# Sheet1.net
KiCad netlist of a schematic drawn in Altium Designer
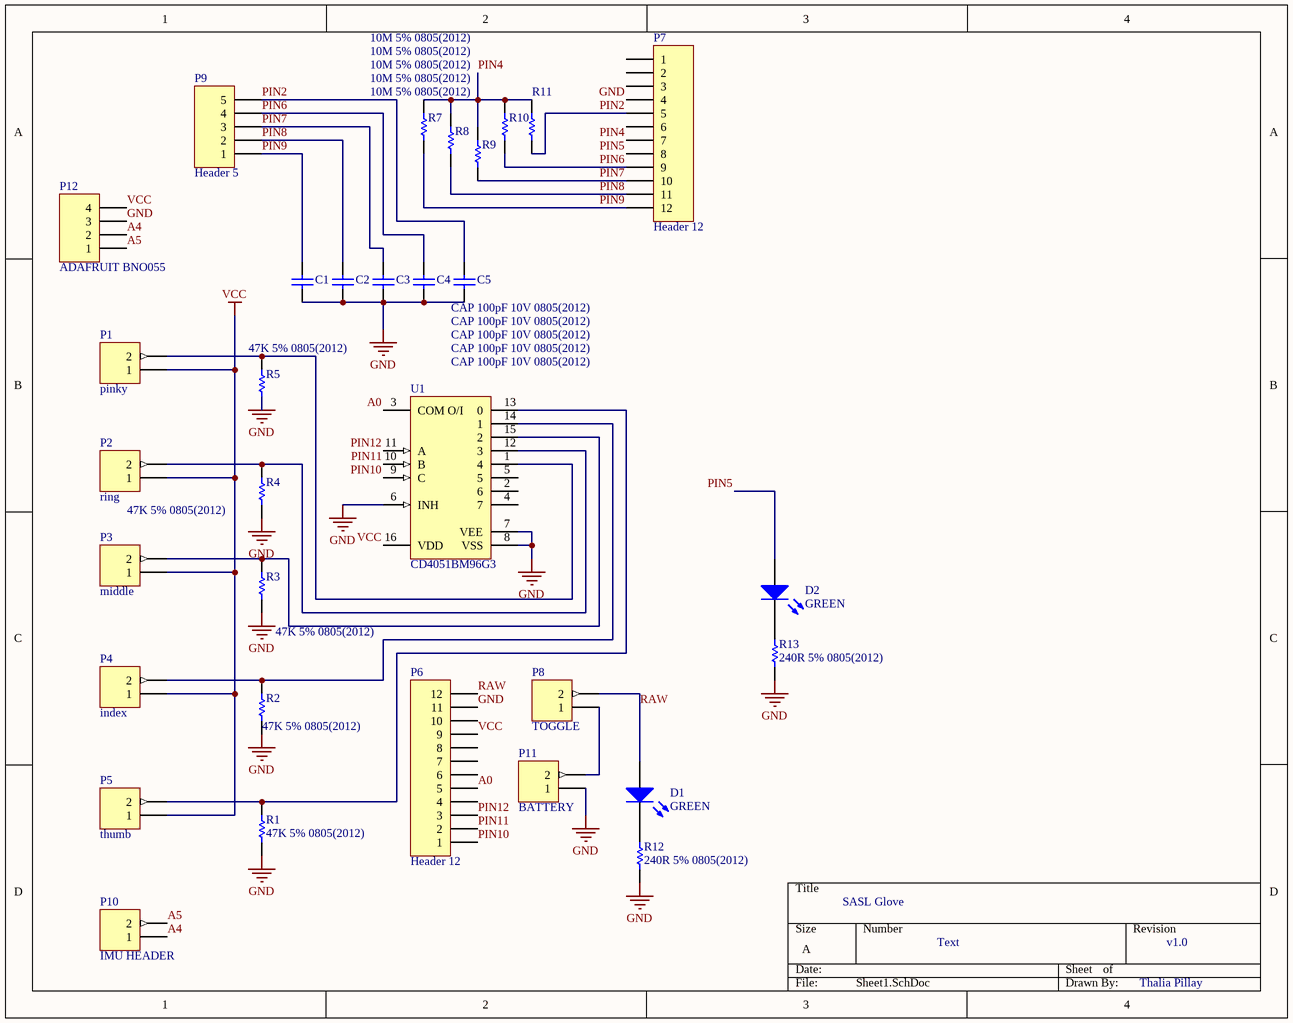
[diagram p0: Sheet1.SchDoc]

(export (version "E")
  (design (tool "Eeschema 10.0.6"))
  (components
    (comp (ref "C1")
      (value "CAP 100pF 10V 0805(2012)")
      (footprint "CAPC0805(2012)100_M")
      (description "CAP 100pF 10V ±5% 0805 (2012 Metric) Thickness 1mm SMD")
      (fields (field (name "TOLERANCE") "Â±5%"))
      (libsource (lib "Altium Content Vault") (part "CAP"))
    )
    (comp (ref "C2")
      (value "CAP 100pF 10V 0805(2012)")
      (footprint "CAPC0805(2012)100_M")
      (description "CAP 100pF 10V ±5% 0805 (2012 Metric) Thickness 1mm SMD")
      (fields (field (name "TOLERANCE") "Â±5%"))
      (libsource (lib "Altium Content Vault") (part "CAP"))
    )
    (comp (ref "C3")
      (value "CAP 100pF 10V 0805(2012)")
      (footprint "CAPC0805(2012)100_M")
      (description "CAP 100pF 10V ±5% 0805 (2012 Metric) Thickness 1mm SMD")
      (fields (field (name "TOLERANCE") "Â±5%"))
      (libsource (lib "Altium Content Vault") (part "CAP"))
    )
    (comp (ref "C4")
      (value "CAP 100pF 10V 0805(2012)")
      (footprint "CAPC0805(2012)100_M")
      (description "CAP 100pF 10V ±5% 0805 (2012 Metric) Thickness 1mm SMD")
      (fields (field (name "TOLERANCE") "Â±5%"))
      (libsource (lib "Altium Content Vault") (part "CAP"))
    )
    (comp (ref "C5")
      (value "CAP 100pF 10V 0805(2012)")
      (footprint "CAPC0805(2012)100_M")
      (description "CAP 100pF 10V ±5% 0805 (2012 Metric) Thickness 1mm SMD")
      (fields (field (name "TOLERANCE") "Â±5%"))
      (libsource (lib "Altium Content Vault") (part "CAP"))
    )
    (comp (ref "D1")
      (value "GREEN")
      (footprint "3.2X1.6X1.1")
      (description "Typical RED, GREEN, YELLOW, AMBER GaAs LED")
      (fields (field (name "PUBLISHER") "Altium Limited"))
      (libsource (lib "Miscellaneous Devices") (part "LED2"))
    )
    (comp (ref "D2")
      (value "GREEN")
      (footprint "3.2X1.6X1.1")
      (description "Typical RED, GREEN, YELLOW, AMBER GaAs LED")
      (fields (field (name "PUBLISHER") "Altium Limited"))
      (libsource (lib "Miscellaneous Devices") (part "LED2"))
    )
    (comp (ref "P1")
      (value "pinky")
      (footprint "HDR1X2")
      (description "Header, 2-Pin")
      (fields (field (name "PUBLISHER") "Altium Limited"))
      (libsource (lib "Miscellaneous Connectors") (part "Header 2"))
    )
    (comp (ref "P2")
      (value "ring")
      (footprint "HDR1X2")
      (description "Header, 2-Pin")
      (fields (field (name "PUBLISHER") "Altium Limited"))
      (libsource (lib "Miscellaneous Connectors") (part "Header 2"))
    )
    (comp (ref "P3")
      (value "middle")
      (footprint "HDR1X2")
      (description "Header, 2-Pin")
      (fields (field (name "PUBLISHER") "Altium Limited"))
      (libsource (lib "Miscellaneous Connectors") (part "Header 2"))
    )
    (comp (ref "P4")
      (value "index")
      (footprint "HDR1X2")
      (description "Header, 2-Pin")
      (fields (field (name "PUBLISHER") "Altium Limited"))
      (libsource (lib "Miscellaneous Connectors") (part "Header 2"))
    )
    (comp (ref "P5")
      (value "thumb")
      (footprint "HDR1X2")
      (description "Header, 2-Pin")
      (fields (field (name "PUBLISHER") "Altium Limited"))
      (libsource (lib "Miscellaneous Connectors") (part "Header 2"))
    )
    (comp (ref "P6")
      (value "Header 12")
      (footprint "HDR1X12")
      (description "Header, 12-Pin")
      (fields (field (name "PUBLISHER") "Altium Limited"))
      (libsource (lib "") (part "Header 12_1"))
    )
    (comp (ref "P7")
      (value "Header 12")
      (footprint "HDR1X12")
      (description "Header, 12-Pin")
      (fields (field (name "PUBLISHER") "Altium Limited"))
      (libsource (lib "Miscellaneous Connectors") (part "Header 12"))
    )
    (comp (ref "P8")
      (value "TOGGLE")
      (footprint "HDR1X2")
      (description "Header, 2-Pin")
      (fields (field (name "PUBLISHER") "Altium Limited"))
      (libsource (lib "Miscellaneous Connectors") (part "Header 2"))
    )
    (comp (ref "P9")
      (value "Header 5")
      (footprint "HDR1X5")
      (description "Header, 5-Pin")
      (fields (field (name "PUBLISHER") "Altium Limited"))
      (libsource (lib "Miscellaneous Connectors") (part "Header 5"))
    )
    (comp (ref "P10")
      (value "IMU HEADER")
      (footprint "HDR1X2")
      (description "Header, 2-Pin")
      (fields (field (name "PUBLISHER") "Altium Limited"))
      (libsource (lib "Miscellaneous Connectors") (part "Header 2"))
    )
    (comp (ref "P11")
      (value "BATTERY")
      (footprint "HDR1X2")
      (description "Header, 2-Pin")
      (fields (field (name "PUBLISHER") "Altium Limited"))
      (libsource (lib "Miscellaneous Connectors") (part "Header 2"))
    )
    (comp (ref "P12")
      (value "ADAFRUIT BNO055")
      (footprint "HDR1X4")
      (description "Header, 4-Pin")
      (fields (field (name "PUBLISHER") "Altium Limited"))
      (libsource (lib "Miscellaneous Connectors") (part "Header 4"))
    )
    (comp (ref "R1")
      (value "47K 5% 0805(2012)")
      (footprint "RESC0805(2012)_L")
      (description "47K 0.125W 5% 0805 (2012 Metric)  SMD")
      (fields (field (name "TOLERANCE") "5 %") (field (name "POWER") "0.125 W"))
      (libsource (lib "Altium Content Vault") (part "RES"))
    )
    (comp (ref "R2")
      (value "47K 5% 0805(2012)")
      (footprint "RESC0805(2012)_L")
      (description "47K 0.125W 5% 0805 (2012 Metric)  SMD")
      (fields (field (name "TOLERANCE") "5 %") (field (name "POWER") "0.125 W"))
      (libsource (lib "Altium Content Vault") (part "RES"))
    )
    (comp (ref "R3")
      (value "47K 5% 0805(2012)")
      (footprint "RESC0805(2012)_L")
      (description "47K 0.125W 5% 0805 (2012 Metric)  SMD")
      (fields (field (name "TOLERANCE") "5 %") (field (name "POWER") "0.125 W"))
      (libsource (lib "Altium Content Vault") (part "RES"))
    )
    (comp (ref "R4")
      (value "47K 5% 0805(2012)")
      (footprint "RESC0805(2012)_L")
      (description "47K 0.125W 5% 0805 (2012 Metric)  SMD")
      (fields (field (name "TOLERANCE") "5 %") (field (name "POWER") "0.125 W"))
      (libsource (lib "Altium Content Vault") (part "RES"))
    )
    (comp (ref "R5")
      (value "47K 5% 0805(2012)")
      (footprint "RESC0805(2012)_L")
      (description "47K 0.125W 5% 0805 (2012 Metric)  SMD")
      (fields (field (name "TOLERANCE") "5 %") (field (name "POWER") "0.125 W"))
      (libsource (lib "Altium Content Vault") (part "RES"))
    )
    (comp (ref "R7")
      (value "10M 5% 0805(2012)")
      (footprint "RESC0805(2012)_M")
      (description "10M 0.125W 5% 0805 (2012 Metric)  SMD")
      (fields (field (name "POWER") "0.125 W") (field (name "TOLERANCE") "5 %"))
      (libsource (lib "Altium Content Vault") (part "RES"))
    )
    (comp (ref "R8")
      (value "10M 5% 0805(2012)")
      (footprint "RESC0805(2012)_M")
      (description "10M 0.125W 5% 0805 (2012 Metric)  SMD")
      (fields (field (name "POWER") "0.125 W") (field (name "TOLERANCE") "5 %"))
      (libsource (lib "Altium Content Vault") (part "RES"))
    )
    (comp (ref "R9")
      (value "10M 5% 0805(2012)")
      (footprint "RESC0805(2012)_M")
      (description "10M 0.125W 5% 0805 (2012 Metric)  SMD")
      (fields (field (name "POWER") "0.125 W") (field (name "TOLERANCE") "5 %"))
      (libsource (lib "Altium Content Vault") (part "RES"))
    )
    (comp (ref "R10")
      (value "10M 5% 0805(2012)")
      (footprint "RESC0805(2012)_M")
      (description "10M 0.125W 5% 0805 (2012 Metric)  SMD")
      (fields (field (name "POWER") "0.125 W") (field (name "TOLERANCE") "5 %"))
      (libsource (lib "Altium Content Vault") (part "RES"))
    )
    (comp (ref "R11")
      (value "10M 5% 0805(2012)")
      (footprint "RESC0805(2012)_M")
      (description "10M 0.125W 5% 0805 (2012 Metric)  SMD")
      (fields (field (name "POWER") "0.125 W") (field (name "TOLERANCE") "5 %"))
      (libsource (lib "Altium Content Vault") (part "RES"))
    )
    (comp (ref "R12")
      (value "240R 5% 0805(2012)")
      (footprint "RESC0805(2012)_N")
      (description "240R 0.125W 5% 0805 (2012 Metric)  SMD")
      (fields (field (name "POWER") "0.125 W") (field (name "TOLERANCE") "5 %"))
      (libsource (lib "Altium Content Vault") (part "RES"))
    )
    (comp (ref "R13")
      (value "240R 5% 0805(2012)")
      (footprint "RESC0805(2012)_N")
      (description "240R 0.125W 5% 0805 (2012 Metric)  SMD")
      (fields (field (name "POWER") "0.125 W") (field (name "TOLERANCE") "5 %"))
      (libsource (lib "Altium Content Vault") (part "RES"))
    )
    (comp (ref "U1")
      (value "CD4051BM96G3")
      (footprint "D0016A_M")
      (fields (field (name "PART NUMBER") "CD4051B"))
      (libsource (lib "Altium Content Vault") (part "TI-CD4051B-16"))
    )
  )
  (nets
    (net (code "1") (name "/A0") (class "Default")
      (node (ref "P6") (pin "5") (pinfunction "5_5") (pintype "passive"))
      (node (ref "U1") (pin "3") (pinfunction "COM_O/I_3") (pintype "passive"))
    )
    (net (code "2") (name "/A4") (class "Default")
      (node (ref "P10") (pin "1") (pinfunction "1_1") (pintype "passive"))
      (node (ref "P12") (pin "2") (pinfunction "2_2") (pintype "passive"))
    )
    (net (code "3") (name "/A5") (class "Default")
      (node (ref "P10") (pin "2") (pinfunction "2_2") (pintype "output"))
      (node (ref "P12") (pin "1") (pinfunction "1_1") (pintype "passive"))
    )
    (net (code "4") (name "/PIN2") (class "Default")
      (node (ref "C5") (pin "2") (pinfunction "2_2") (pintype "passive"))
      (node (ref "P7") (pin "5") (pinfunction "5_5") (pintype "passive"))
      (node (ref "P9") (pin "5") (pinfunction "5_5") (pintype "passive"))
      (node (ref "R11") (pin "1") (pinfunction "1_1") (pintype "passive"))
    )
    (net (code "5") (name "/PIN4") (class "Default")
      (node (ref "P7") (pin "7") (pinfunction "7_7") (pintype "passive"))
      (node (ref "R10") (pin "2") (pinfunction "2_2") (pintype "passive"))
      (node (ref "R11") (pin "2") (pinfunction "2_2") (pintype "passive"))
      (node (ref "R7") (pin "2") (pinfunction "2_2") (pintype "passive"))
      (node (ref "R8") (pin "2") (pinfunction "2_2") (pintype "passive"))
      (node (ref "R9") (pin "2") (pinfunction "2_2") (pintype "passive"))
    )
    (net (code "6") (name "/PIN5") (class "Default")
      (node (ref "D2") (pin "1") (pinfunction "A_1") (pintype "passive"))
      (node (ref "P7") (pin "8") (pinfunction "8_8") (pintype "passive"))
    )
    (net (code "7") (name "/PIN6") (class "Default")
      (node (ref "C4") (pin "2") (pinfunction "2_2") (pintype "passive"))
      (node (ref "P7") (pin "9") (pinfunction "9_9") (pintype "passive"))
      (node (ref "P9") (pin "4") (pinfunction "4_4") (pintype "passive"))
      (node (ref "R10") (pin "1") (pinfunction "1_1") (pintype "passive"))
    )
    (net (code "8") (name "/PIN7") (class "Default")
      (node (ref "C3") (pin "2") (pinfunction "2_2") (pintype "passive"))
      (node (ref "P7") (pin "10") (pinfunction "10_10") (pintype "passive"))
      (node (ref "P9") (pin "3") (pinfunction "3_3") (pintype "passive"))
      (node (ref "R9") (pin "1") (pinfunction "1_1") (pintype "passive"))
    )
    (net (code "9") (name "/PIN8") (class "Default")
      (node (ref "C2") (pin "2") (pinfunction "2_2") (pintype "passive"))
      (node (ref "P7") (pin "11") (pinfunction "11_11") (pintype "passive"))
      (node (ref "P9") (pin "2") (pinfunction "2_2") (pintype "passive"))
      (node (ref "R8") (pin "1") (pinfunction "1_1") (pintype "passive"))
    )
    (net (code "10") (name "/PIN9") (class "Default")
      (node (ref "C1") (pin "2") (pinfunction "2_2") (pintype "passive"))
      (node (ref "P7") (pin "12") (pinfunction "12_12") (pintype "passive"))
      (node (ref "P9") (pin "1") (pinfunction "1_1") (pintype "passive"))
      (node (ref "R7") (pin "1") (pinfunction "1_1") (pintype "passive"))
    )
    (net (code "11") (name "/PIN10") (class "Default")
      (node (ref "P6") (pin "1") (pinfunction "1_1") (pintype "passive"))
      (node (ref "U1") (pin "9") (pinfunction "C_9") (pintype "input"))
    )
    (net (code "12") (name "/PIN11") (class "Default")
      (node (ref "P6") (pin "2") (pinfunction "2_2") (pintype "passive"))
      (node (ref "U1") (pin "10") (pinfunction "B_10") (pintype "input"))
    )
    (net (code "13") (name "/PIN12") (class "Default")
      (node (ref "P6") (pin "3") (pinfunction "3_3") (pintype "passive"))
      (node (ref "U1") (pin "11") (pinfunction "A_11") (pintype "input"))
    )
    (net (code "14") (name "/RAW") (class "Default")
      (node (ref "D1") (pin "1") (pinfunction "A_1") (pintype "passive"))
      (node (ref "P6") (pin "12") (pinfunction "12_12") (pintype "passive"))
      (node (ref "P8") (pin "2") (pinfunction "2_2") (pintype "output"))
    )
    (net (code "15") (name "GND") (class "Default")
      (node (ref "C1") (pin "1") (pinfunction "1_1") (pintype "passive"))
      (node (ref "C2") (pin "1") (pinfunction "1_1") (pintype "passive"))
      (node (ref "C3") (pin "1") (pinfunction "1_1") (pintype "passive"))
      (node (ref "C4") (pin "1") (pinfunction "1_1") (pintype "passive"))
      (node (ref "C5") (pin "1") (pinfunction "1_1") (pintype "passive"))
      (node (ref "P11") (pin "1") (pinfunction "1_1") (pintype "passive"))
      (node (ref "P12") (pin "3") (pinfunction "3_3") (pintype "passive"))
      (node (ref "P6") (pin "11") (pinfunction "11_11") (pintype "passive"))
      (node (ref "P7") (pin "4") (pinfunction "4_4") (pintype "passive"))
      (node (ref "R1") (pin "1") (pinfunction "1_1") (pintype "passive"))
      (node (ref "R12") (pin "1") (pinfunction "1_1") (pintype "passive"))
      (node (ref "R13") (pin "1") (pinfunction "1_1") (pintype "passive"))
      (node (ref "R2") (pin "1") (pinfunction "1_1") (pintype "passive"))
      (node (ref "R3") (pin "1") (pinfunction "1_1") (pintype "passive"))
      (node (ref "R4") (pin "1") (pinfunction "1_1") (pintype "passive"))
      (node (ref "R5") (pin "1") (pinfunction "1_1") (pintype "passive"))
      (node (ref "U1") (pin "6") (pinfunction "INH_6") (pintype "input"))
      (node (ref "U1") (pin "7") (pinfunction "VEE_7") (pintype "power_in"))
      (node (ref "U1") (pin "8") (pinfunction "VSS_8") (pintype "power_in"))
    )
    (net (code "16") (name "Net-(D1-K)") (class "Default")
      (node (ref "D1") (pin "2") (pinfunction "K_2") (pintype "passive"))
      (node (ref "R12") (pin "2") (pinfunction "2_2") (pintype "passive"))
    )
    (net (code "17") (name "Net-(D2-K)") (class "Default")
      (node (ref "D2") (pin "2") (pinfunction "K_2") (pintype "passive"))
      (node (ref "R13") (pin "2") (pinfunction "2_2") (pintype "passive"))
    )
    (net (code "18") (name "Net-(P11-Pad2)") (class "Default")
      (node (ref "P11") (pin "2") (pinfunction "2_2") (pintype "output"))
      (node (ref "P8") (pin "1") (pinfunction "1_1") (pintype "passive"))
    )
    (net (code "19") (name "Net-(U1-0)") (class "Default")
      (node (ref "P5") (pin "2") (pinfunction "2_2") (pintype "output"))
      (node (ref "R1") (pin "2") (pinfunction "2_2") (pintype "passive"))
      (node (ref "U1") (pin "13") (pinfunction "0_13") (pintype "passive"))
    )
    (net (code "20") (name "Net-(U1-1)") (class "Default")
      (node (ref "P4") (pin "2") (pinfunction "2_2") (pintype "output"))
      (node (ref "R2") (pin "2") (pinfunction "2_2") (pintype "passive"))
      (node (ref "U1") (pin "14") (pinfunction "1_14") (pintype "passive"))
    )
    (net (code "21") (name "Net-(U1-2)") (class "Default")
      (node (ref "P3") (pin "2") (pinfunction "2_2") (pintype "output"))
      (node (ref "R3") (pin "2") (pinfunction "2_2") (pintype "passive"))
      (node (ref "U1") (pin "15") (pinfunction "2_15") (pintype "passive"))
    )
    (net (code "22") (name "Net-(U1-3)") (class "Default")
      (node (ref "P2") (pin "2") (pinfunction "2_2") (pintype "output"))
      (node (ref "R4") (pin "2") (pinfunction "2_2") (pintype "passive"))
      (node (ref "U1") (pin "12") (pinfunction "3_12") (pintype "passive"))
    )
    (net (code "23") (name "Net-(U1-4)") (class "Default")
      (node (ref "P1") (pin "2") (pinfunction "2_2") (pintype "output"))
      (node (ref "R5") (pin "2") (pinfunction "2_2") (pintype "passive"))
      (node (ref "U1") (pin "1") (pinfunction "4_1") (pintype "passive"))
    )
    (net (code "24") (name "VCC") (class "Default")
      (node (ref "P1") (pin "1") (pinfunction "1_1") (pintype "passive"))
      (node (ref "P12") (pin "4") (pinfunction "4_4") (pintype "passive"))
      (node (ref "P2") (pin "1") (pinfunction "1_1") (pintype "passive"))
      (node (ref "P3") (pin "1") (pinfunction "1_1") (pintype "passive"))
      (node (ref "P4") (pin "1") (pinfunction "1_1") (pintype "passive"))
      (node (ref "P5") (pin "1") (pinfunction "1_1") (pintype "passive"))
      (node (ref "P6") (pin "9") (pinfunction "9_9") (pintype "passive"))
      (node (ref "U1") (pin "16") (pinfunction "VDD_16") (pintype "power_in"))
    )
    (net (code "25") (name "unconnected-(P6-Pad4)") (class "Default")
      (node (ref "P6") (pin "4") (pinfunction "4_4") (pintype "passive"))
    )
    (net (code "26") (name "unconnected-(P6-Pad6)") (class "Default")
      (node (ref "P6") (pin "6") (pinfunction "6_6") (pintype "passive"))
    )
    (net (code "27") (name "unconnected-(P6-Pad7)") (class "Default")
      (node (ref "P6") (pin "7") (pinfunction "7_7") (pintype "passive"))
    )
    (net (code "28") (name "unconnected-(P6-Pad8)") (class "Default")
      (node (ref "P6") (pin "8") (pinfunction "8_8") (pintype "passive"))
    )
    (net (code "29") (name "unconnected-(P6-Pad10)") (class "Default")
      (node (ref "P6") (pin "10") (pinfunction "10_10") (pintype "passive"))
    )
    (net (code "30") (name "unconnected-(P7-Pad1)") (class "Default")
      (node (ref "P7") (pin "1") (pinfunction "1_1") (pintype "passive"))
    )
    (net (code "31") (name "unconnected-(P7-Pad2)") (class "Default")
      (node (ref "P7") (pin "2") (pinfunction "2_2") (pintype "passive"))
    )
    (net (code "32") (name "unconnected-(P7-Pad3)") (class "Default")
      (node (ref "P7") (pin "3") (pinfunction "3_3") (pintype "passive"))
    )
    (net (code "33") (name "unconnected-(P7-Pad6)") (class "Default")
      (node (ref "P7") (pin "6") (pinfunction "6_6") (pintype "passive"))
    )
    (net (code "34") (name "unconnected-(U1-6-Pad2)") (class "Default")
      (node (ref "U1") (pin "2") (pinfunction "6_2") (pintype "passive"))
    )
    (net (code "35") (name "unconnected-(U1-7-Pad4)") (class "Default")
      (node (ref "U1") (pin "4") (pinfunction "7_4") (pintype "passive"))
    )
    (net (code "36") (name "unconnected-(U1-Pad5)") (class "Default")
      (node (ref "U1") (pin "5") (pinfunction "5_5") (pintype "passive"))
    )
  )
)
